# Schematic.net
KiCad netlist of a schematic drawn in Altium Designer
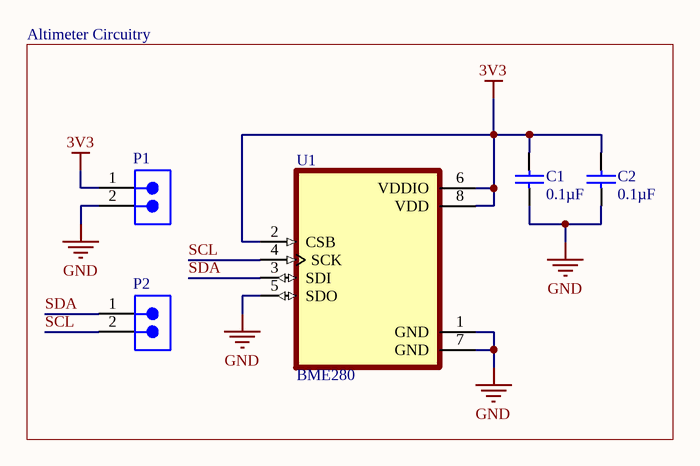
[diagram p0: Schematic.SchDoc]

(export (version "E")
  (design (tool "Eeschema 10.0.6"))
  (components
    (comp (ref "C1")
      (value "0.1µF")
      (footprint "CAPC3216X100X50LL20T25")
      (description "Chip Capacitor, 100 nF, +/- 10%, 25 V, -55 to 125 degC, 1206 (3216 Metric), RoHS, Tape and Reel")
      (fields (field (name "MANUFACTURER") "Kemet"))
      (libsource (lib "Altium Content Vault") (part "CAP-NP-2"))
    )
    (comp (ref "C2")
      (value "0.1µF")
      (footprint "CAPC3216X100X50LL20T25")
      (description "Chip Capacitor, 100 nF, +/- 10%, 25 V, -55 to 125 degC, 1206 (3216 Metric), RoHS, Tape and Reel")
      (fields (field (name "MANUFACTURER") "Kemet"))
      (libsource (lib "Altium Content Vault") (part "CAP-NP-2"))
    )
    (comp (ref "P1")
      (value "61300211121")
      (footprint "61300211121")
      (libsource (lib "Altium Content Vault") (part "Header_Male_1R_02P"))
    )
    (comp (ref "P2")
      (value "61300211121")
      (footprint "61300211121")
      (libsource (lib "Altium Content Vault") (part "Header_Male_1R_02P"))
    )
    (comp (ref "U1")
      (value "BME280")
      (footprint "PSON65P250X250X100-8N")
      (libsource (lib "BME280") (part "BME280"))
    )
  )
  (nets
    (net (code "1") (name "/SCL") (class "Default")
      (node (ref "P2") (pin "2") (pinfunction "2_2") (pintype "passive"))
      (node (ref "U1") (pin "4") (pinfunction "SCK_4") (pintype "input"))
    )
    (net (code "2") (name "/SDA") (class "Default")
      (node (ref "P2") (pin "1") (pinfunction "1_1") (pintype "passive"))
      (node (ref "U1") (pin "3") (pinfunction "SDI_3") (pintype "bidirectional"))
    )
    (net (code "3") (name "3V3") (class "Default")
      (node (ref "C1") (pin "1") (pinfunction "1_1") (pintype "passive"))
      (node (ref "C2") (pin "1") (pinfunction "1_1") (pintype "passive"))
      (node (ref "P1") (pin "1") (pinfunction "1_1") (pintype "passive"))
      (node (ref "U1") (pin "2") (pinfunction "CSB_2") (pintype "input"))
      (node (ref "U1") (pin "6") (pinfunction "VDDIO_6") (pintype "power_in"))
      (node (ref "U1") (pin "8") (pinfunction "VDD_8") (pintype "power_in"))
    )
    (net (code "4") (name "GND") (class "Default")
      (node (ref "C1") (pin "2") (pinfunction "2_2") (pintype "passive"))
      (node (ref "C2") (pin "2") (pinfunction "2_2") (pintype "passive"))
      (node (ref "P1") (pin "2") (pinfunction "2_2") (pintype "passive"))
      (node (ref "U1") (pin "1") (pinfunction "GND_1") (pintype "power_in"))
      (node (ref "U1") (pin "5") (pinfunction "SDO_5") (pintype "bidirectional"))
      (node (ref "U1") (pin "7") (pinfunction "GND_7") (pintype "power_in"))
    )
  )
)
